# ProPrj_haxmasday2_2025-12-15.net
KiCad netlist of a schematic drawn in EasyEDA Pro
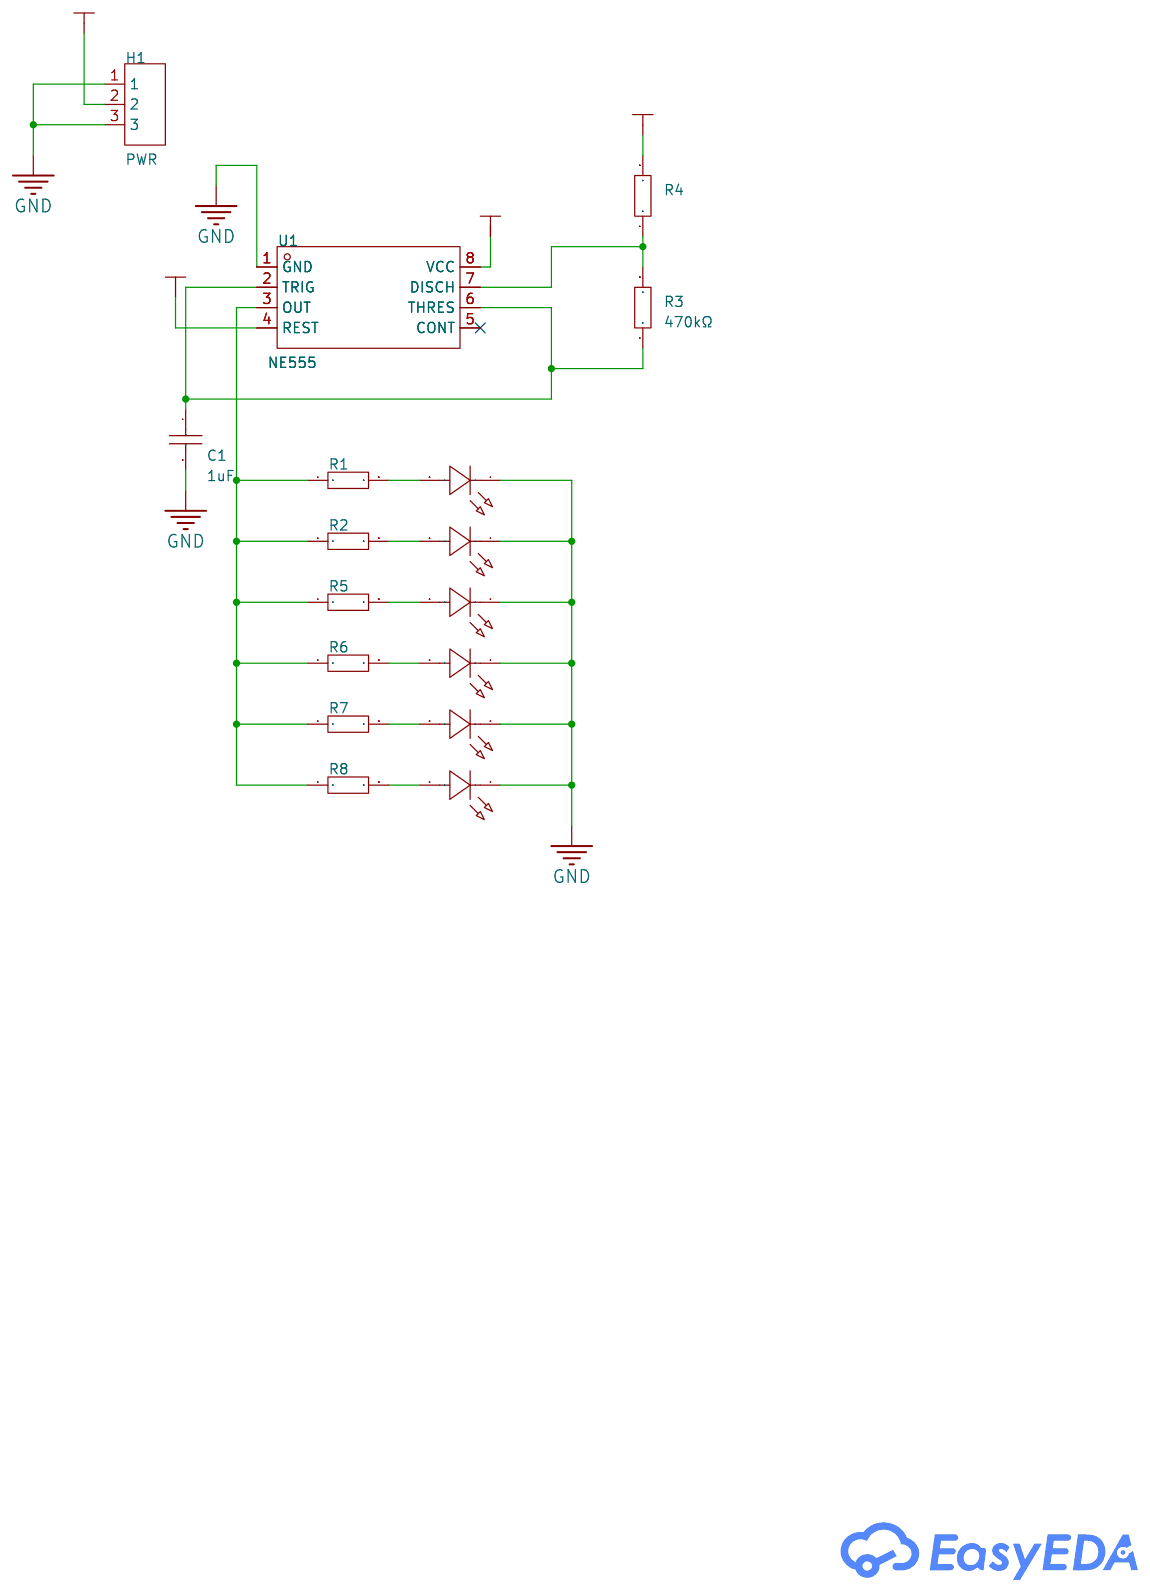
[diagram p0: schematic sheet]

(export (version "E")
  (design (tool "Eeschema 10.0.6"))
  (components
    (comp (ref "C1")
      (value "1uF")
      (footprint "easyedapro:CAP-TH_L7.3-W4.5-P5.00-D0.5")
      (fields (field (name "Manufacturer Part") "B32529C0105J289") (field (name "Manufacturer") "TDK"))
      (libsource (lib "easyedapro") (part "B32529C0105J289"))
    )
    (comp (ref "H1")
      (value "PWR")
      (footprint "easyedapro:HDR-TH_3P-P2.54-V-M-1")
      (fields (field (name "Manufacturer") "hanxia(韩下)"))
      (libsource (lib "easyedapro") (part "HX PH254-01-03-Z-L11.5 PCB PIN HEADER"))
    )
    (comp (ref "LED1")
      (value "XL-302SURD")
      (footprint "easyedapro:LED-TH_BD3.8-P2.54-RD")
      (fields (field (name "Manufacturer") "XINGLIGHT(成兴光)"))
      (libsource (lib "easyedapro") (part "XL-302SURD"))
    )
    (comp (ref "LED2")
      (value "XL-302SURD")
      (footprint "easyedapro:LED-TH_BD3.8-P2.54-RD")
      (fields (field (name "Manufacturer") "XINGLIGHT(成兴光)"))
      (libsource (lib "easyedapro") (part "XL-302SURD"))
    )
    (comp (ref "LED3")
      (value "XL-302SURD")
      (footprint "easyedapro:LED-TH_BD3.8-P2.54-RD")
      (fields (field (name "Manufacturer") "XINGLIGHT(成兴光)"))
      (libsource (lib "easyedapro") (part "XL-302SURD"))
    )
    (comp (ref "LED4")
      (value "XL-302SURD")
      (footprint "easyedapro:LED-TH_BD3.8-P2.54-RD")
      (fields (field (name "Manufacturer") "XINGLIGHT(成兴光)"))
      (libsource (lib "easyedapro") (part "XL-302SURD"))
    )
    (comp (ref "LED5")
      (value "XL-302SURD")
      (footprint "easyedapro:LED-TH_BD3.8-P2.54-RD")
      (fields (field (name "Manufacturer") "XINGLIGHT(成兴光)"))
      (libsource (lib "easyedapro") (part "XL-302SURD"))
    )
    (comp (ref "LED6")
      (value "XL-302SURD")
      (footprint "easyedapro:LED-TH_BD3.8-P2.54-RD")
      (fields (field (name "Manufacturer") "XINGLIGHT(成兴光)"))
      (libsource (lib "easyedapro") (part "XL-302SURD"))
    )
    (comp (ref "R1")
      (value "1kΩ")
      (footprint "easyedapro:RES-TH_BD2.5-L6.5-P10.50-D0.6")
      (fields
        (field (name "Manufacturer Part") "MFR0W4F1001A50")
        (field (name "Manufacturer") "UNI-ROYAL(厚声)")
      )
      (libsource (lib "easyedapro") (part "MFR0W4F1001A50"))
    )
    (comp (ref "R2")
      (value "1kΩ")
      (footprint "easyedapro:RES-TH_BD2.5-L6.5-P10.50-D0.6")
      (fields
        (field (name "Manufacturer Part") "MFR0W4F1001A50")
        (field (name "Manufacturer") "UNI-ROYAL(厚声)")
      )
      (libsource (lib "easyedapro") (part "MFR0W4F1001A50"))
    )
    (comp (ref "R3")
      (value "470kΩ")
      (footprint "easyedapro:RES-TH_BD2.2-L6.5-P10.50-D0.6")
      (fields (field (name "Manufacturer Part") "MFR50SJT-52-470K") (field (name "Manufacturer") "YAGEO(国巨)"))
      (libsource (lib "easyedapro") (part "MFR50SJT-52-470K"))
    )
    (comp (ref "R4")
      (value "1kΩ")
      (footprint "easyedapro:RES-TH_BD2.5-L6.5-P10.50-D0.6")
      (fields
        (field (name "Manufacturer Part") "MFR0W4F1001A50")
        (field (name "Manufacturer") "UNI-ROYAL(厚声)")
      )
      (libsource (lib "easyedapro") (part "MFR0W4F1001A50"))
    )
    (comp (ref "R5")
      (value "1kΩ")
      (footprint "easyedapro:RES-TH_BD2.5-L6.5-P10.50-D0.6")
      (fields
        (field (name "Manufacturer Part") "MFR0W4F1001A50")
        (field (name "Manufacturer") "UNI-ROYAL(厚声)")
      )
      (libsource (lib "easyedapro") (part "MFR0W4F1001A50"))
    )
    (comp (ref "R6")
      (value "1kΩ")
      (footprint "easyedapro:RES-TH_BD2.5-L6.5-P10.50-D0.6")
      (fields
        (field (name "Manufacturer Part") "MFR0W4F1001A50")
        (field (name "Manufacturer") "UNI-ROYAL(厚声)")
      )
      (libsource (lib "easyedapro") (part "MFR0W4F1001A50"))
    )
    (comp (ref "R7")
      (value "1kΩ")
      (footprint "easyedapro:RES-TH_BD2.5-L6.5-P10.50-D0.6")
      (fields
        (field (name "Manufacturer Part") "MFR0W4F1001A50")
        (field (name "Manufacturer") "UNI-ROYAL(厚声)")
      )
      (libsource (lib "easyedapro") (part "MFR0W4F1001A50"))
    )
    (comp (ref "R8")
      (value "1kΩ")
      (footprint "easyedapro:RES-TH_BD2.5-L6.5-P10.50-D0.6")
      (fields
        (field (name "Manufacturer Part") "MFR0W4F1001A50")
        (field (name "Manufacturer") "UNI-ROYAL(厚声)")
      )
      (libsource (lib "easyedapro") (part "MFR0W4F1001A50"))
    )
    (comp (ref "U1")
      (value "NE555")
      (footprint "easyedapro:DIP-8_L9.7-W6.4-P2.54-LS7.6-BL")
      (libsource (lib "easyedapro") (part "NE555_C504550"))
    )
  )
  (nets
    (net (code "1") (name "9V") (class "Default")
      (node (ref "H1") (pin "2") (pinfunction "2_2") (pintype "unspecified"))
      (node (ref "R4") (pin "2") (pinfunction "2_2") (pintype "input"))
      (node (ref "U1") (pin "4") (pinfunction "REST_4") (pintype "unspecified"))
      (node (ref "U1") (pin "8") (pinfunction "VCC_8") (pintype "unspecified"))
    )
    (net (code "2") (name "GND") (class "Default")
      (node (ref "C1") (pin "2") (pinfunction "2_2") (pintype "input"))
      (node (ref "H1") (pin "1") (pinfunction "1_1") (pintype "unspecified"))
      (node (ref "H1") (pin "3") (pinfunction "3_3") (pintype "unspecified"))
      (node (ref "LED1") (pin "1") (pinfunction "K_1") (pintype "unspecified"))
      (node (ref "LED2") (pin "1") (pinfunction "K_1") (pintype "unspecified"))
      (node (ref "LED3") (pin "1") (pinfunction "K_1") (pintype "unspecified"))
      (node (ref "LED4") (pin "1") (pinfunction "K_1") (pintype "unspecified"))
      (node (ref "LED5") (pin "1") (pinfunction "K_1") (pintype "unspecified"))
      (node (ref "LED6") (pin "1") (pinfunction "K_1") (pintype "unspecified"))
      (node (ref "U1") (pin "1") (pinfunction "GND_1") (pintype "unspecified"))
    )
    (net (code "3") (name "Net-(LED1-A)") (class "Default")
      (node (ref "LED1") (pin "2") (pinfunction "A_2") (pintype "unspecified"))
      (node (ref "R1") (pin "2") (pinfunction "2_2") (pintype "input"))
    )
    (net (code "4") (name "Net-(LED2-A)") (class "Default")
      (node (ref "LED2") (pin "2") (pinfunction "A_2") (pintype "unspecified"))
      (node (ref "R2") (pin "2") (pinfunction "2_2") (pintype "input"))
    )
    (net (code "5") (name "Net-(LED3-A)") (class "Default")
      (node (ref "LED3") (pin "2") (pinfunction "A_2") (pintype "unspecified"))
      (node (ref "R5") (pin "2") (pinfunction "2_2") (pintype "input"))
    )
    (net (code "6") (name "Net-(LED4-A)") (class "Default")
      (node (ref "LED4") (pin "2") (pinfunction "A_2") (pintype "unspecified"))
      (node (ref "R6") (pin "2") (pinfunction "2_2") (pintype "input"))
    )
    (net (code "7") (name "Net-(LED5-A)") (class "Default")
      (node (ref "LED5") (pin "2") (pinfunction "A_2") (pintype "unspecified"))
      (node (ref "R7") (pin "2") (pinfunction "2_2") (pintype "input"))
    )
    (net (code "8") (name "Net-(LED6-A)") (class "Default")
      (node (ref "LED6") (pin "2") (pinfunction "A_2") (pintype "unspecified"))
      (node (ref "R8") (pin "2") (pinfunction "2_2") (pintype "input"))
    )
    (net (code "9") (name "Net-(U1-DISCH)") (class "Default")
      (node (ref "R3") (pin "2") (pinfunction "2_2") (pintype "unspecified"))
      (node (ref "R4") (pin "1") (pinfunction "1_1") (pintype "input"))
      (node (ref "U1") (pin "7") (pinfunction "DISCH_7") (pintype "unspecified"))
    )
    (net (code "10") (name "Net-(U1-OUT)") (class "Default")
      (node (ref "R1") (pin "1") (pinfunction "1_1") (pintype "input"))
      (node (ref "R2") (pin "1") (pinfunction "1_1") (pintype "input"))
      (node (ref "R5") (pin "1") (pinfunction "1_1") (pintype "input"))
      (node (ref "R6") (pin "1") (pinfunction "1_1") (pintype "input"))
      (node (ref "R7") (pin "1") (pinfunction "1_1") (pintype "input"))
      (node (ref "R8") (pin "1") (pinfunction "1_1") (pintype "input"))
      (node (ref "U1") (pin "3") (pinfunction "OUT_3") (pintype "unspecified"))
    )
    (net (code "11") (name "Net-(U1-THRES)") (class "Default")
      (node (ref "C1") (pin "1") (pinfunction "1_1") (pintype "input"))
      (node (ref "R3") (pin "1") (pinfunction "1_1") (pintype "unspecified"))
      (node (ref "U1") (pin "2") (pinfunction "TRIG_2") (pintype "unspecified"))
      (node (ref "U1") (pin "6") (pinfunction "THRES_6") (pintype "unspecified"))
    )
    (net (code "12") (name "unconnected-(U1-CONT-Pad5)") (class "Default")
      (node (ref "U1") (pin "5") (pinfunction "CONT_5") (pintype "unspecified+no_connect"))
    )
  )
)
